# CPU_Logic.net
KiCad netlist of a schematic drawn in Altium Designer
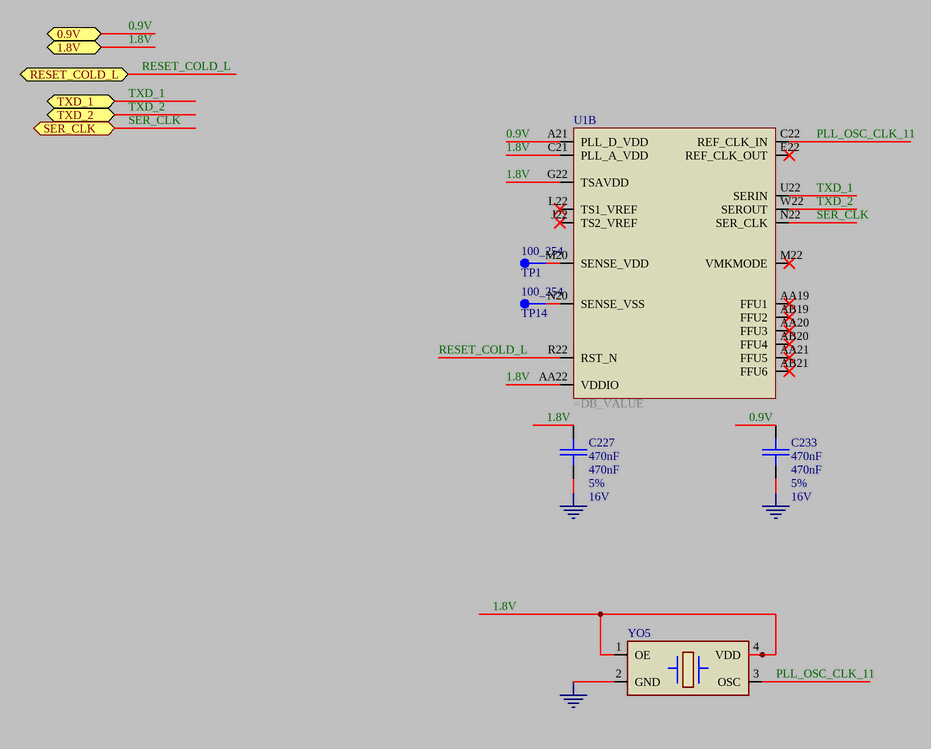
[diagram p0: CPU_Logic.SchDoc]

(export (version "E")
  (design (tool "Eeschema 10.0.6"))
  (components
    (comp (ref "C227")
      (value "470nF")
      (footprint "SMD_0603_CAPC1608X95N")
      (fields
        (field (name "DB_PART_NUMBER") "CAP000028169")
        (field (name "DB_VALUE") "470nF")
        (field (name "DB_TOLERANCE") "5%")
        (field (name "DB_VOLTAGE") "16V")
        (field (name "DB_MANUFACTURER_PART") "KEMET    C0603C474J4RAC")
        (field (name "DB_APPROVED_BY") "ISHIDDEN=T")
      )
      (libsource (lib "Database_Libs1") (part "C"))
    )
    (comp (ref "C233")
      (value "470nF")
      (footprint "SMD_0603_CAPC1608X95N")
      (fields
        (field (name "DB_PART_NUMBER") "CAP000028169")
        (field (name "DB_VALUE") "470nF")
        (field (name "DB_TOLERANCE") "5%")
        (field (name "DB_VOLTAGE") "16V")
        (field (name "DB_MANUFACTURER_PART") "KEMET    C0603C474J4RAC")
        (field (name "DB_APPROVED_BY") "ISHIDDEN=T")
      )
      (libsource (lib "Database_Libs1") (part "C"))
    )
    (comp (ref "TP1")
      (value "100_254")
      (footprint "SMD_TP_100-254")
      (fields
        (field (name "DB_PART_NUMBER") "TPO000000001")
        (field (name "DB_MANUFACTURER_PART") "ISHIDDEN=T")
        (field (name "DB_APPROVED_BY") "ISHIDDEN=T")
      )
      (libsource (lib "Database_Libs1") (part "TEST_POINT_1"))
    )
    (comp (ref "TP14")
      (value "100_254")
      (footprint "SMD_TP_100-254")
      (fields
        (field (name "DB_PART_NUMBER") "TPO000000001")
        (field (name "DB_MANUFACTURER_PART") "ISHIDDEN=T")
        (field (name "DB_APPROVED_BY") "ISHIDDEN=T")
      )
      (libsource (lib "Database_Libs1") (part "TEST_POINT_1"))
    )
    (comp (ref "U1")
      (value "~")
      (footprint "SMD_BGA480C80P22X22")
      (libsource (lib "RockerBox") (part "IC_RockerBox"))
    )
    (comp (ref "YO5")
      (value "~")
      (footprint "SMD_OSCCF250X320X90-4N")
      (libsource (lib "RockerBox") (part "XTAL_OE1GND2OSC3VDD4"))
    )
  )
  (nets
    (net (code "1") (name "/0.9V") (class "Default")
      (node (ref "C233") (pin "2") (pinfunction "2_2") (pintype "passive"))
      (node (ref "U1") (pin "A21") (pinfunction "PLL_D_VDD_A21") (pintype "passive"))
    )
    (net (code "2") (name "/1.8V") (class "Default")
      (node (ref "C227") (pin "2") (pinfunction "2_2") (pintype "passive"))
      (node (ref "U1") (pin "AA22") (pinfunction "VDDIO_AA22") (pintype "passive"))
      (node (ref "U1") (pin "C21") (pinfunction "PLL_A_VDD_C21") (pintype "passive"))
      (node (ref "U1") (pin "G22") (pinfunction "TSAVDD_G22") (pintype "passive"))
      (node (ref "YO5") (pin "1") (pinfunction "OE_1") (pintype "passive"))
      (node (ref "YO5") (pin "4") (pinfunction "VDD_4") (pintype "passive"))
    )
    (net (code "3") (name "/PLL_OSC_CLK_11") (class "Default")
      (node (ref "U1") (pin "C22") (pinfunction "REF_CLK_IN_C22") (pintype "passive"))
      (node (ref "YO5") (pin "3") (pinfunction "OSC_3") (pintype "passive"))
    )
    (net (code "4") (name "/RESET_COLD_L") (class "Default")
      (node (ref "U1") (pin "R22") (pinfunction "RST_N_R22") (pintype "passive"))
    )
    (net (code "5") (name "/SER_CLK") (class "Default")
      (node (ref "U1") (pin "N22") (pinfunction "SER_CLK_N22") (pintype "passive"))
    )
    (net (code "6") (name "/TXD_1") (class "Default")
      (node (ref "U1") (pin "U22") (pinfunction "SERIN_U22") (pintype "passive"))
    )
    (net (code "7") (name "/TXD_2") (class "Default")
      (node (ref "U1") (pin "W22") (pinfunction "SEROUT_W22") (pintype "passive"))
    )
    (net (code "8") (name "GND") (class "Default")
      (node (ref "C227") (pin "1") (pinfunction "1_1") (pintype "passive"))
      (node (ref "C233") (pin "1") (pinfunction "1_1") (pintype "passive"))
      (node (ref "YO5") (pin "2") (pinfunction "GND_2") (pintype "passive"))
    )
    (net (code "9") (name "Net-(U1B-SENSE_VDD)") (class "Default")
      (node (ref "TP1") (pin "1") (pinfunction "1_1") (pintype "passive"))
      (node (ref "U1") (pin "M20") (pinfunction "SENSE_VDD_M20") (pintype "passive"))
    )
    (net (code "10") (name "Net-(U1B-SENSE_VSS)") (class "Default")
      (node (ref "TP14") (pin "1") (pinfunction "1_1") (pintype "passive"))
      (node (ref "U1") (pin "N20") (pinfunction "SENSE_VSS_N20") (pintype "passive"))
    )
    (net (code "11") (name "unconnected-(U1B-FFU1-PadAA19)") (class "Default")
      (node (ref "U1") (pin "AA19") (pinfunction "FFU1_AA19") (pintype "passive+no_connect"))
    )
    (net (code "12") (name "unconnected-(U1B-FFU2-PadAB19)") (class "Default")
      (node (ref "U1") (pin "AB19") (pinfunction "FFU2_AB19") (pintype "passive+no_connect"))
    )
    (net (code "13") (name "unconnected-(U1B-FFU3-PadAA20)") (class "Default")
      (node (ref "U1") (pin "AA20") (pinfunction "FFU3_AA20") (pintype "passive+no_connect"))
    )
    (net (code "14") (name "unconnected-(U1B-FFU4-PadAB20)") (class "Default")
      (node (ref "U1") (pin "AB20") (pinfunction "FFU4_AB20") (pintype "passive+no_connect"))
    )
    (net (code "15") (name "unconnected-(U1B-FFU5-PadAA21)") (class "Default")
      (node (ref "U1") (pin "AA21") (pinfunction "FFU5_AA21") (pintype "passive+no_connect"))
    )
    (net (code "16") (name "unconnected-(U1B-FFU6-PadAB21)") (class "Default")
      (node (ref "U1") (pin "AB21") (pinfunction "FFU6_AB21") (pintype "passive+no_connect"))
    )
    (net (code "17") (name "unconnected-(U1B-REF_CLK_OUT-PadE22)") (class "Default")
      (node (ref "U1") (pin "E22") (pinfunction "REF_CLK_OUT_E22") (pintype "passive+no_connect"))
    )
    (net (code "18") (name "unconnected-(U1B-TS1_VREF-PadL22)") (class "Default")
      (node (ref "U1") (pin "L22") (pinfunction "TS1_VREF_L22") (pintype "passive+no_connect"))
    )
    (net (code "19") (name "unconnected-(U1B-TS2_VREF-PadJ22)") (class "Default")
      (node (ref "U1") (pin "J22") (pinfunction "TS2_VREF_J22") (pintype "passive+no_connect"))
    )
    (net (code "20") (name "unconnected-(U1B-VMKMODE-PadM22)") (class "Default")
      (node (ref "U1") (pin "M22") (pinfunction "VMKMODE_M22") (pintype "passive+no_connect"))
    )
  )
)
